# Pure_Power_Strip.net
KiCad netlist of a schematic drawn in EAGLE
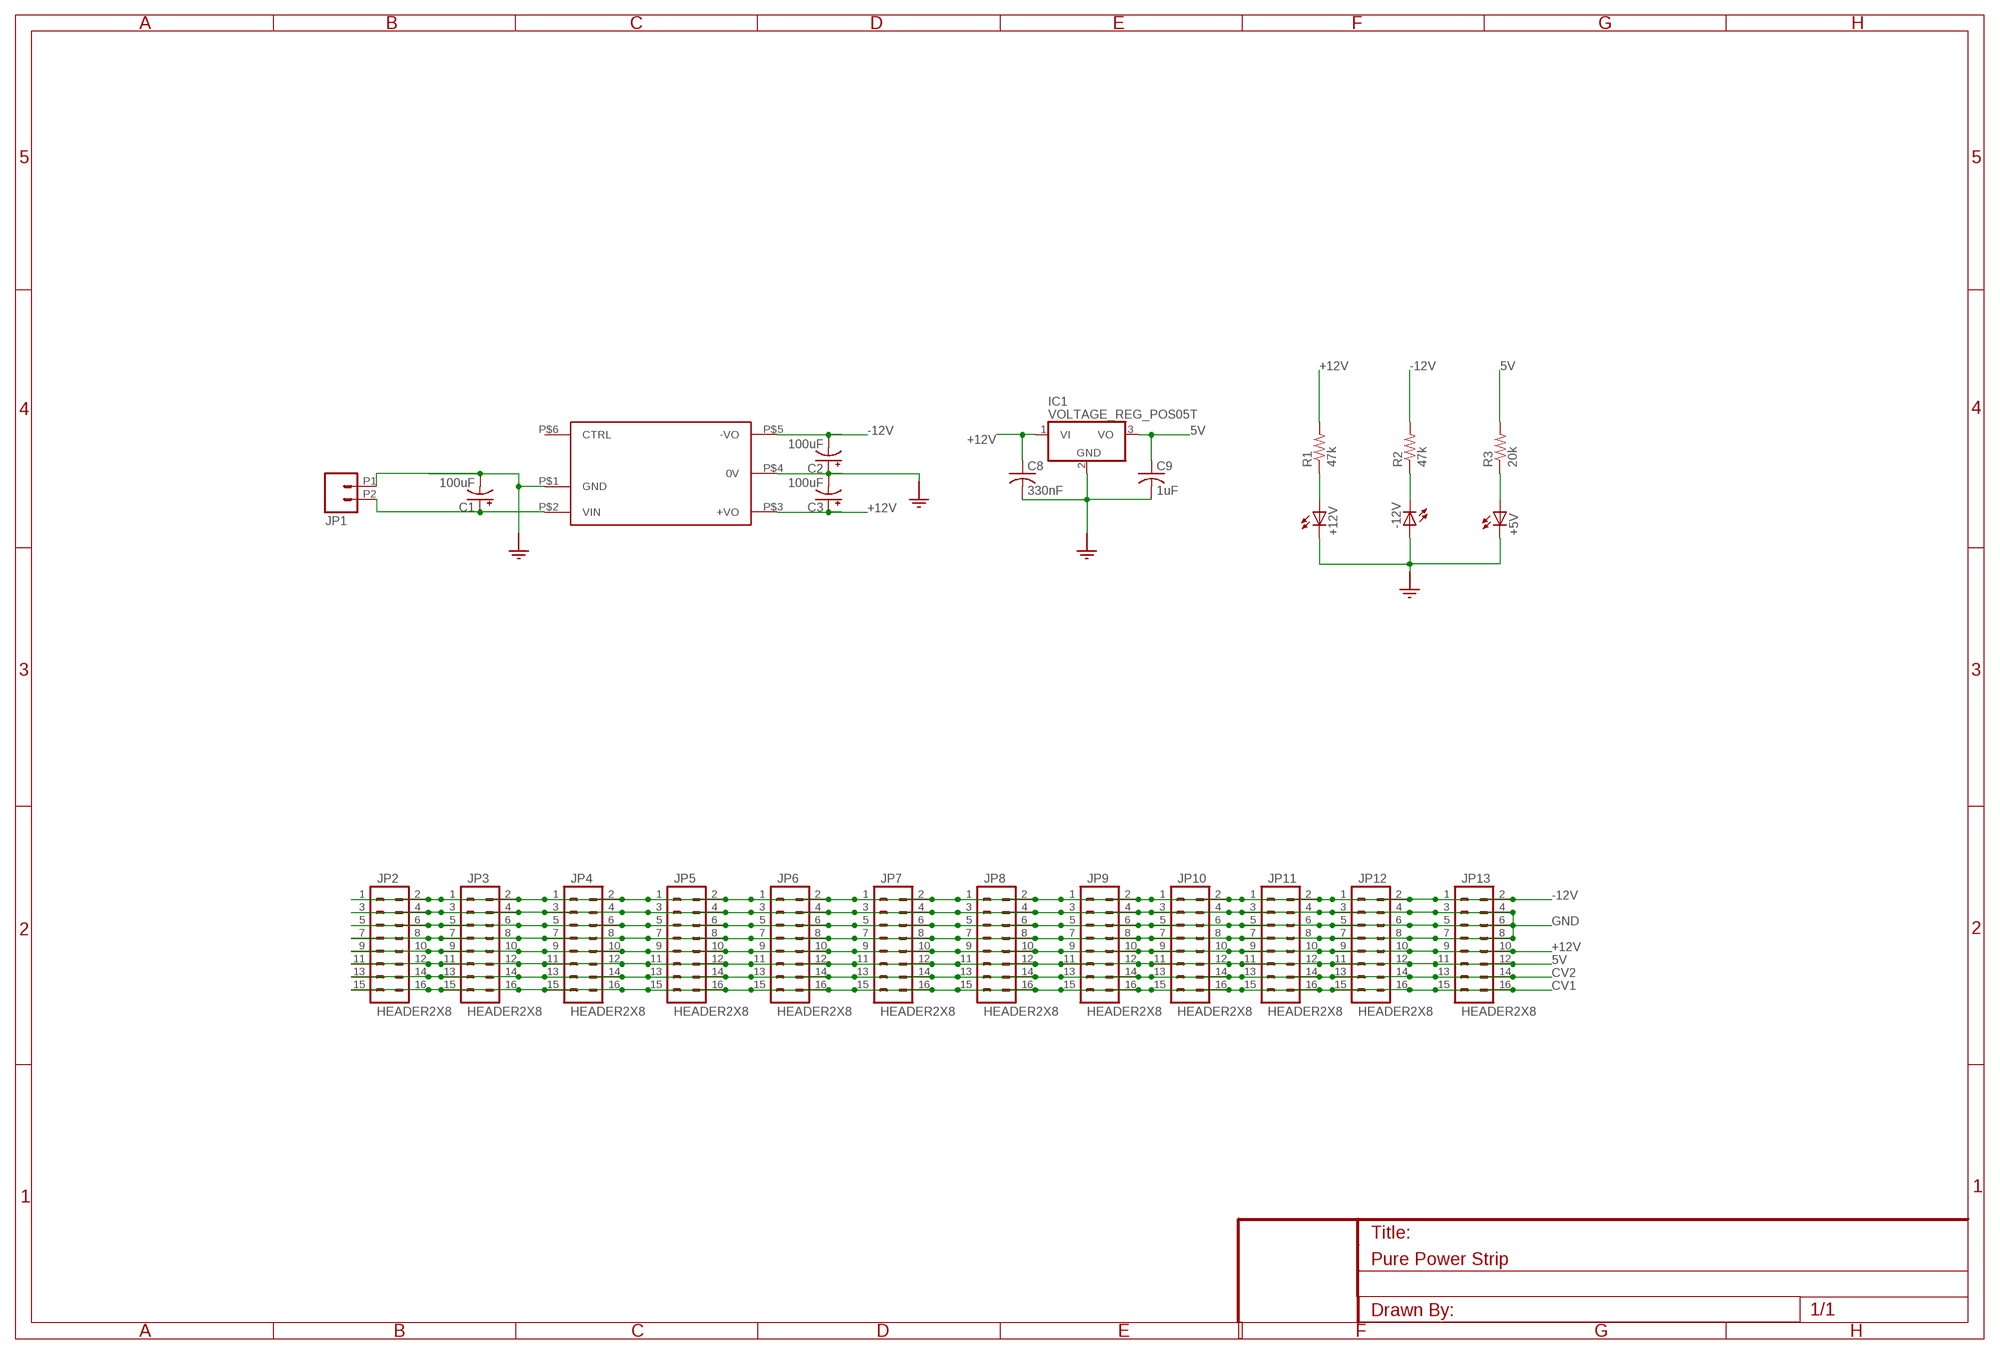
[diagram p0: schematic, sheet 1]

(export (version "E")
  (design (tool "Eeschema 10.0.6"))
  (components
    (comp (ref "+5V")
      (value "LED5MM")
      (footprint "eagle-import:LED5MM")
      (libsource (lib "eagle-import") (part "LED5MM"))
    )
    (comp (ref "+12V")
      (value "LED5MM")
      (footprint "eagle-import:LED5MM")
      (libsource (lib "eagle-import") (part "LED5MM"))
    )
    (comp (ref "-12V")
      (value "LED5MM")
      (footprint "eagle-import:LED5MM")
      (libsource (lib "eagle-import") (part "LED5MM"))
    )
    (comp (ref "C1")
      (value "100uF")
      (footprint "eagle-import:0511_2.24")
      (libsource (lib "eagle-import") (part "CAPACITOR_POL-US0511/2.24"))
    )
    (comp (ref "C2")
      (value "100uF")
      (footprint "eagle-import:0511_2.24")
      (libsource (lib "eagle-import") (part "CAPACITOR_POL-US0511/2.24"))
    )
    (comp (ref "C3")
      (value "100uF")
      (footprint "eagle-import:0511_2.24")
      (libsource (lib "eagle-import") (part "CAPACITOR_POL-US0511/2.24"))
    )
    (comp (ref "C8")
      (value "330nF")
      (footprint "eagle-import:C025-024X044")
      (libsource (lib "eagle-import") (part "CAPACITOR-US025-024X044"))
    )
    (comp (ref "C9")
      (value "1uF")
      (footprint "eagle-import:C025-024X044")
      (libsource (lib "eagle-import") (part "CAPACITOR-US025-024X044"))
    )
    (comp (ref "IC1")
      (value "VOLTAGE_REG_POS05T")
      (footprint "eagle-import:TO220H")
      (libsource (lib "eagle-import") (part "VOLTAGE_REG_POST05"))
    )
    (comp (ref "JP1")
      (value "HEADER1X25MM_SCREWTERM")
      (footprint "eagle-import:1X02_5MM_SCREWTERM")
      (libsource (lib "eagle-import") (part "HEADER1X25MM_SCREWTERM"))
    )
    (comp (ref "JP2")
      (value "HEADER2X8")
      (footprint "eagle-import:POWER_SHROUDED")
      (libsource (lib "eagle-import") (part "HEADER2X8"))
    )
    (comp (ref "JP3")
      (value "HEADER2X8")
      (footprint "eagle-import:POWER_SHROUDED")
      (libsource (lib "eagle-import") (part "HEADER2X8"))
    )
    (comp (ref "JP4")
      (value "HEADER2X8")
      (footprint "eagle-import:POWER_SHROUDED")
      (libsource (lib "eagle-import") (part "HEADER2X8"))
    )
    (comp (ref "JP5")
      (value "HEADER2X8")
      (footprint "eagle-import:POWER_SHROUDED")
      (libsource (lib "eagle-import") (part "HEADER2X8"))
    )
    (comp (ref "JP6")
      (value "HEADER2X8")
      (footprint "eagle-import:POWER_SHROUDED")
      (libsource (lib "eagle-import") (part "HEADER2X8"))
    )
    (comp (ref "JP7")
      (value "HEADER2X8")
      (footprint "eagle-import:POWER_SHROUDED")
      (libsource (lib "eagle-import") (part "HEADER2X8"))
    )
    (comp (ref "JP8")
      (value "HEADER2X8")
      (footprint "eagle-import:POWER_SHROUDED")
      (libsource (lib "eagle-import") (part "HEADER2X8"))
    )
    (comp (ref "JP9")
      (value "HEADER2X8")
      (footprint "eagle-import:POWER_SHROUDED")
      (libsource (lib "eagle-import") (part "HEADER2X8"))
    )
    (comp (ref "JP10")
      (value "HEADER2X8")
      (footprint "eagle-import:POWER_SHROUDED")
      (libsource (lib "eagle-import") (part "HEADER2X8"))
    )
    (comp (ref "JP11")
      (value "HEADER2X8")
      (footprint "eagle-import:POWER_SHROUDED")
      (libsource (lib "eagle-import") (part "HEADER2X8"))
    )
    (comp (ref "JP12")
      (value "HEADER2X8")
      (footprint "eagle-import:POWER_SHROUDED")
      (libsource (lib "eagle-import") (part "HEADER2X8"))
    )
    (comp (ref "JP13")
      (value "HEADER2X8")
      (footprint "eagle-import:POWER_SHROUDED")
      (libsource (lib "eagle-import") (part "HEADER2X8"))
    )
    (comp (ref "R1")
      (value "47k")
      (footprint "eagle-import:0207_8.5")
      (libsource (lib "eagle-import") (part "RESISTOR_US0207/8.5"))
    )
    (comp (ref "R2")
      (value "47k")
      (footprint "eagle-import:0207_8.5")
      (libsource (lib "eagle-import") (part "RESISTOR_US0207/8.5"))
    )
    (comp (ref "R3")
      (value "20k")
      (footprint "eagle-import:0207_8.5")
      (libsource (lib "eagle-import") (part "RESISTOR_US0207/8.5"))
    )
    (comp (ref "U$1")
      (value "DCDC_CONVERTER_URA241XLD-20WR3")
      (footprint "eagle-import:URA241XLD-20WR3")
      (libsource (lib "eagle-import") (part "DCDC_CONVERTER_URA241XLD-20WR3"))
    )
  )
  (nets
    (net (code "1") (name "/+12V") (class "Default")
      (node (ref "C3") (pin "P$2") (pinfunction "+_P$2") (pintype "passive"))
      (node (ref "C8") (pin "1") (pinfunction "1_1") (pintype "passive"))
      (node (ref "IC1") (pin "1") (pinfunction "VI_1") (pintype "input"))
      (node (ref "JP10") (pin "10") (pinfunction "10_10") (pintype "passive"))
      (node (ref "JP10") (pin "9") (pinfunction "9_9") (pintype "passive"))
      (node (ref "JP11") (pin "10") (pinfunction "10_10") (pintype "passive"))
      (node (ref "JP11") (pin "9") (pinfunction "9_9") (pintype "passive"))
      (node (ref "JP12") (pin "10") (pinfunction "10_10") (pintype "passive"))
      (node (ref "JP12") (pin "9") (pinfunction "9_9") (pintype "passive"))
      (node (ref "JP13") (pin "10") (pinfunction "10_10") (pintype "passive"))
      (node (ref "JP13") (pin "9") (pinfunction "9_9") (pintype "passive"))
      (node (ref "JP2") (pin "10") (pinfunction "10_10") (pintype "passive"))
      (node (ref "JP2") (pin "9") (pinfunction "9_9") (pintype "passive"))
      (node (ref "JP3") (pin "10") (pinfunction "10_10") (pintype "passive"))
      (node (ref "JP3") (pin "9") (pinfunction "9_9") (pintype "passive"))
      (node (ref "JP4") (pin "10") (pinfunction "10_10") (pintype "passive"))
      (node (ref "JP4") (pin "9") (pinfunction "9_9") (pintype "passive"))
      (node (ref "JP5") (pin "10") (pinfunction "10_10") (pintype "passive"))
      (node (ref "JP5") (pin "9") (pinfunction "9_9") (pintype "passive"))
      (node (ref "JP6") (pin "10") (pinfunction "10_10") (pintype "passive"))
      (node (ref "JP6") (pin "9") (pinfunction "9_9") (pintype "passive"))
      (node (ref "JP7") (pin "10") (pinfunction "10_10") (pintype "passive"))
      (node (ref "JP7") (pin "9") (pinfunction "9_9") (pintype "passive"))
      (node (ref "JP8") (pin "10") (pinfunction "10_10") (pintype "passive"))
      (node (ref "JP8") (pin "9") (pinfunction "9_9") (pintype "passive"))
      (node (ref "JP9") (pin "10") (pinfunction "10_10") (pintype "passive"))
      (node (ref "JP9") (pin "9") (pinfunction "9_9") (pintype "passive"))
      (node (ref "R1") (pin "2") (pinfunction "2_2") (pintype "passive"))
      (node (ref "U$1") (pin "P$3") (pinfunction "+VO_P$3") (pintype "bidirectional"))
    )
    (net (code "2") (name "/-12V") (class "Default")
      (node (ref "C2") (pin "P$1") (pinfunction "-_P$1") (pintype "passive"))
      (node (ref "JP10") (pin "1") (pinfunction "1_1") (pintype "passive"))
      (node (ref "JP10") (pin "2") (pinfunction "2_2") (pintype "passive"))
      (node (ref "JP11") (pin "1") (pinfunction "1_1") (pintype "passive"))
      (node (ref "JP11") (pin "2") (pinfunction "2_2") (pintype "passive"))
      (node (ref "JP12") (pin "1") (pinfunction "1_1") (pintype "passive"))
      (node (ref "JP12") (pin "2") (pinfunction "2_2") (pintype "passive"))
      (node (ref "JP13") (pin "1") (pinfunction "1_1") (pintype "passive"))
      (node (ref "JP13") (pin "2") (pinfunction "2_2") (pintype "passive"))
      (node (ref "JP2") (pin "1") (pinfunction "1_1") (pintype "passive"))
      (node (ref "JP2") (pin "2") (pinfunction "2_2") (pintype "passive"))
      (node (ref "JP3") (pin "1") (pinfunction "1_1") (pintype "passive"))
      (node (ref "JP3") (pin "2") (pinfunction "2_2") (pintype "passive"))
      (node (ref "JP4") (pin "1") (pinfunction "1_1") (pintype "passive"))
      (node (ref "JP4") (pin "2") (pinfunction "2_2") (pintype "passive"))
      (node (ref "JP5") (pin "1") (pinfunction "1_1") (pintype "passive"))
      (node (ref "JP5") (pin "2") (pinfunction "2_2") (pintype "passive"))
      (node (ref "JP6") (pin "1") (pinfunction "1_1") (pintype "passive"))
      (node (ref "JP6") (pin "2") (pinfunction "2_2") (pintype "passive"))
      (node (ref "JP7") (pin "1") (pinfunction "1_1") (pintype "passive"))
      (node (ref "JP7") (pin "2") (pinfunction "2_2") (pintype "passive"))
      (node (ref "JP8") (pin "1") (pinfunction "1_1") (pintype "passive"))
      (node (ref "JP8") (pin "2") (pinfunction "2_2") (pintype "passive"))
      (node (ref "JP9") (pin "1") (pinfunction "1_1") (pintype "passive"))
      (node (ref "JP9") (pin "2") (pinfunction "2_2") (pintype "passive"))
      (node (ref "R2") (pin "2") (pinfunction "2_2") (pintype "passive"))
      (node (ref "U$1") (pin "P$5") (pinfunction "-VO_P$5") (pintype "bidirectional"))
    )
    (net (code "3") (name "/5V") (class "Default")
      (node (ref "C9") (pin "1") (pinfunction "1_1") (pintype "passive"))
      (node (ref "IC1") (pin "3") (pinfunction "VO_3") (pintype "passive"))
      (node (ref "JP10") (pin "11") (pinfunction "11_11") (pintype "passive"))
      (node (ref "JP10") (pin "12") (pinfunction "12_12") (pintype "passive"))
      (node (ref "JP11") (pin "11") (pinfunction "11_11") (pintype "passive"))
      (node (ref "JP11") (pin "12") (pinfunction "12_12") (pintype "passive"))
      (node (ref "JP12") (pin "11") (pinfunction "11_11") (pintype "passive"))
      (node (ref "JP12") (pin "12") (pinfunction "12_12") (pintype "passive"))
      (node (ref "JP13") (pin "11") (pinfunction "11_11") (pintype "passive"))
      (node (ref "JP13") (pin "12") (pinfunction "12_12") (pintype "passive"))
      (node (ref "JP2") (pin "11") (pinfunction "11_11") (pintype "passive"))
      (node (ref "JP2") (pin "12") (pinfunction "12_12") (pintype "passive"))
      (node (ref "JP3") (pin "11") (pinfunction "11_11") (pintype "passive"))
      (node (ref "JP3") (pin "12") (pinfunction "12_12") (pintype "passive"))
      (node (ref "JP4") (pin "11") (pinfunction "11_11") (pintype "passive"))
      (node (ref "JP4") (pin "12") (pinfunction "12_12") (pintype "passive"))
      (node (ref "JP5") (pin "11") (pinfunction "11_11") (pintype "passive"))
      (node (ref "JP5") (pin "12") (pinfunction "12_12") (pintype "passive"))
      (node (ref "JP6") (pin "11") (pinfunction "11_11") (pintype "passive"))
      (node (ref "JP6") (pin "12") (pinfunction "12_12") (pintype "passive"))
      (node (ref "JP7") (pin "11") (pinfunction "11_11") (pintype "passive"))
      (node (ref "JP7") (pin "12") (pinfunction "12_12") (pintype "passive"))
      (node (ref "JP8") (pin "11") (pinfunction "11_11") (pintype "passive"))
      (node (ref "JP8") (pin "12") (pinfunction "12_12") (pintype "passive"))
      (node (ref "JP9") (pin "11") (pinfunction "11_11") (pintype "passive"))
      (node (ref "JP9") (pin "12") (pinfunction "12_12") (pintype "passive"))
      (node (ref "R3") (pin "2") (pinfunction "2_2") (pintype "passive"))
    )
    (net (code "4") (name "/CV1") (class "Default")
      (node (ref "JP10") (pin "15") (pinfunction "15_15") (pintype "passive"))
      (node (ref "JP10") (pin "16") (pinfunction "16_16") (pintype "passive"))
      (node (ref "JP11") (pin "15") (pinfunction "15_15") (pintype "passive"))
      (node (ref "JP11") (pin "16") (pinfunction "16_16") (pintype "passive"))
      (node (ref "JP12") (pin "15") (pinfunction "15_15") (pintype "passive"))
      (node (ref "JP12") (pin "16") (pinfunction "16_16") (pintype "passive"))
      (node (ref "JP13") (pin "15") (pinfunction "15_15") (pintype "passive"))
      (node (ref "JP13") (pin "16") (pinfunction "16_16") (pintype "passive"))
      (node (ref "JP2") (pin "15") (pinfunction "15_15") (pintype "passive"))
      (node (ref "JP2") (pin "16") (pinfunction "16_16") (pintype "passive"))
      (node (ref "JP3") (pin "15") (pinfunction "15_15") (pintype "passive"))
      (node (ref "JP3") (pin "16") (pinfunction "16_16") (pintype "passive"))
      (node (ref "JP4") (pin "15") (pinfunction "15_15") (pintype "passive"))
      (node (ref "JP4") (pin "16") (pinfunction "16_16") (pintype "passive"))
      (node (ref "JP5") (pin "15") (pinfunction "15_15") (pintype "passive"))
      (node (ref "JP5") (pin "16") (pinfunction "16_16") (pintype "passive"))
      (node (ref "JP6") (pin "15") (pinfunction "15_15") (pintype "passive"))
      (node (ref "JP6") (pin "16") (pinfunction "16_16") (pintype "passive"))
      (node (ref "JP7") (pin "15") (pinfunction "15_15") (pintype "passive"))
      (node (ref "JP7") (pin "16") (pinfunction "16_16") (pintype "passive"))
      (node (ref "JP8") (pin "15") (pinfunction "15_15") (pintype "passive"))
      (node (ref "JP8") (pin "16") (pinfunction "16_16") (pintype "passive"))
      (node (ref "JP9") (pin "15") (pinfunction "15_15") (pintype "passive"))
      (node (ref "JP9") (pin "16") (pinfunction "16_16") (pintype "passive"))
    )
    (net (code "5") (name "/CV2") (class "Default")
      (node (ref "JP10") (pin "13") (pinfunction "13_13") (pintype "passive"))
      (node (ref "JP10") (pin "14") (pinfunction "14_14") (pintype "passive"))
      (node (ref "JP11") (pin "13") (pinfunction "13_13") (pintype "passive"))
      (node (ref "JP11") (pin "14") (pinfunction "14_14") (pintype "passive"))
      (node (ref "JP12") (pin "13") (pinfunction "13_13") (pintype "passive"))
      (node (ref "JP12") (pin "14") (pinfunction "14_14") (pintype "passive"))
      (node (ref "JP13") (pin "13") (pinfunction "13_13") (pintype "passive"))
      (node (ref "JP13") (pin "14") (pinfunction "14_14") (pintype "passive"))
      (node (ref "JP2") (pin "13") (pinfunction "13_13") (pintype "passive"))
      (node (ref "JP2") (pin "14") (pinfunction "14_14") (pintype "passive"))
      (node (ref "JP3") (pin "13") (pinfunction "13_13") (pintype "passive"))
      (node (ref "JP3") (pin "14") (pinfunction "14_14") (pintype "passive"))
      (node (ref "JP4") (pin "13") (pinfunction "13_13") (pintype "passive"))
      (node (ref "JP4") (pin "14") (pinfunction "14_14") (pintype "passive"))
      (node (ref "JP5") (pin "13") (pinfunction "13_13") (pintype "passive"))
      (node (ref "JP5") (pin "14") (pinfunction "14_14") (pintype "passive"))
      (node (ref "JP6") (pin "13") (pinfunction "13_13") (pintype "passive"))
      (node (ref "JP6") (pin "14") (pinfunction "14_14") (pintype "passive"))
      (node (ref "JP7") (pin "13") (pinfunction "13_13") (pintype "passive"))
      (node (ref "JP7") (pin "14") (pinfunction "14_14") (pintype "passive"))
      (node (ref "JP8") (pin "13") (pinfunction "13_13") (pintype "passive"))
      (node (ref "JP8") (pin "14") (pinfunction "14_14") (pintype "passive"))
      (node (ref "JP9") (pin "13") (pinfunction "13_13") (pintype "passive"))
      (node (ref "JP9") (pin "14") (pinfunction "14_14") (pintype "passive"))
    )
    (net (code "6") (name "GND") (class "Default")
      (node (ref "+12V") (pin "K") (pinfunction "C_K") (pintype "passive"))
      (node (ref "+5V") (pin "K") (pinfunction "C_K") (pintype "passive"))
      (node (ref "-12V") (pin "A") (pinfunction "A_A") (pintype "passive"))
      (node (ref "C1") (pin "P$1") (pinfunction "-_P$1") (pintype "passive"))
      (node (ref "C2") (pin "P$2") (pinfunction "+_P$2") (pintype "passive"))
      (node (ref "C3") (pin "P$1") (pinfunction "-_P$1") (pintype "passive"))
      (node (ref "C8") (pin "2") (pinfunction "2_2") (pintype "passive"))
      (node (ref "C9") (pin "2") (pinfunction "2_2") (pintype "passive"))
      (node (ref "IC1") (pin "2") (pinfunction "GND_2") (pintype "passive"))
      (node (ref "JP1") (pin "P1") (pinfunction "1_P1") (pintype "passive"))
      (node (ref "JP10") (pin "3") (pinfunction "3_3") (pintype "passive"))
      (node (ref "JP10") (pin "4") (pinfunction "4_4") (pintype "passive"))
      (node (ref "JP10") (pin "5") (pinfunction "5_5") (pintype "passive"))
      (node (ref "JP10") (pin "6") (pinfunction "6_6") (pintype "passive"))
      (node (ref "JP10") (pin "7") (pinfunction "7_7") (pintype "passive"))
      (node (ref "JP10") (pin "8") (pinfunction "8_8") (pintype "passive"))
      (node (ref "JP11") (pin "3") (pinfunction "3_3") (pintype "passive"))
      (node (ref "JP11") (pin "4") (pinfunction "4_4") (pintype "passive"))
      (node (ref "JP11") (pin "5") (pinfunction "5_5") (pintype "passive"))
      (node (ref "JP11") (pin "6") (pinfunction "6_6") (pintype "passive"))
      (node (ref "JP11") (pin "7") (pinfunction "7_7") (pintype "passive"))
      (node (ref "JP11") (pin "8") (pinfunction "8_8") (pintype "passive"))
      (node (ref "JP12") (pin "3") (pinfunction "3_3") (pintype "passive"))
      (node (ref "JP12") (pin "4") (pinfunction "4_4") (pintype "passive"))
      (node (ref "JP12") (pin "5") (pinfunction "5_5") (pintype "passive"))
      (node (ref "JP12") (pin "6") (pinfunction "6_6") (pintype "passive"))
      (node (ref "JP12") (pin "7") (pinfunction "7_7") (pintype "passive"))
      (node (ref "JP12") (pin "8") (pinfunction "8_8") (pintype "passive"))
      (node (ref "JP13") (pin "3") (pinfunction "3_3") (pintype "passive"))
      (node (ref "JP13") (pin "4") (pinfunction "4_4") (pintype "passive"))
      (node (ref "JP13") (pin "5") (pinfunction "5_5") (pintype "passive"))
      (node (ref "JP13") (pin "6") (pinfunction "6_6") (pintype "passive"))
      (node (ref "JP13") (pin "7") (pinfunction "7_7") (pintype "passive"))
      (node (ref "JP13") (pin "8") (pinfunction "8_8") (pintype "passive"))
      (node (ref "JP2") (pin "3") (pinfunction "3_3") (pintype "passive"))
      (node (ref "JP2") (pin "4") (pinfunction "4_4") (pintype "passive"))
      (node (ref "JP2") (pin "5") (pinfunction "5_5") (pintype "passive"))
      (node (ref "JP2") (pin "6") (pinfunction "6_6") (pintype "passive"))
      (node (ref "JP2") (pin "7") (pinfunction "7_7") (pintype "passive"))
      (node (ref "JP2") (pin "8") (pinfunction "8_8") (pintype "passive"))
      (node (ref "JP3") (pin "3") (pinfunction "3_3") (pintype "passive"))
      (node (ref "JP3") (pin "4") (pinfunction "4_4") (pintype "passive"))
      (node (ref "JP3") (pin "5") (pinfunction "5_5") (pintype "passive"))
      (node (ref "JP3") (pin "6") (pinfunction "6_6") (pintype "passive"))
      (node (ref "JP3") (pin "7") (pinfunction "7_7") (pintype "passive"))
      (node (ref "JP3") (pin "8") (pinfunction "8_8") (pintype "passive"))
      (node (ref "JP4") (pin "3") (pinfunction "3_3") (pintype "passive"))
      (node (ref "JP4") (pin "4") (pinfunction "4_4") (pintype "passive"))
      (node (ref "JP4") (pin "5") (pinfunction "5_5") (pintype "passive"))
      (node (ref "JP4") (pin "6") (pinfunction "6_6") (pintype "passive"))
      (node (ref "JP4") (pin "7") (pinfunction "7_7") (pintype "passive"))
      (node (ref "JP4") (pin "8") (pinfunction "8_8") (pintype "passive"))
      (node (ref "JP5") (pin "3") (pinfunction "3_3") (pintype "passive"))
      (node (ref "JP5") (pin "4") (pinfunction "4_4") (pintype "passive"))
      (node (ref "JP5") (pin "5") (pinfunction "5_5") (pintype "passive"))
      (node (ref "JP5") (pin "6") (pinfunction "6_6") (pintype "passive"))
      (node (ref "JP5") (pin "7") (pinfunction "7_7") (pintype "passive"))
      (node (ref "JP5") (pin "8") (pinfunction "8_8") (pintype "passive"))
      (node (ref "JP6") (pin "3") (pinfunction "3_3") (pintype "passive"))
      (node (ref "JP6") (pin "4") (pinfunction "4_4") (pintype "passive"))
      (node (ref "JP6") (pin "5") (pinfunction "5_5") (pintype "passive"))
      (node (ref "JP6") (pin "6") (pinfunction "6_6") (pintype "passive"))
      (node (ref "JP6") (pin "7") (pinfunction "7_7") (pintype "passive"))
      (node (ref "JP6") (pin "8") (pinfunction "8_8") (pintype "passive"))
      (node (ref "JP7") (pin "3") (pinfunction "3_3") (pintype "passive"))
      (node (ref "JP7") (pin "4") (pinfunction "4_4") (pintype "passive"))
      (node (ref "JP7") (pin "5") (pinfunction "5_5") (pintype "passive"))
      (node (ref "JP7") (pin "6") (pinfunction "6_6") (pintype "passive"))
      (node (ref "JP7") (pin "7") (pinfunction "7_7") (pintype "passive"))
      (node (ref "JP7") (pin "8") (pinfunction "8_8") (pintype "passive"))
      (node (ref "JP8") (pin "3") (pinfunction "3_3") (pintype "passive"))
      (node (ref "JP8") (pin "4") (pinfunction "4_4") (pintype "passive"))
      (node (ref "JP8") (pin "5") (pinfunction "5_5") (pintype "passive"))
      (node (ref "JP8") (pin "6") (pinfunction "6_6") (pintype "passive"))
      (node (ref "JP8") (pin "7") (pinfunction "7_7") (pintype "passive"))
      (node (ref "JP8") (pin "8") (pinfunction "8_8") (pintype "passive"))
      (node (ref "JP9") (pin "3") (pinfunction "3_3") (pintype "passive"))
      (node (ref "JP9") (pin "4") (pinfunction "4_4") (pintype "passive"))
      (node (ref "JP9") (pin "5") (pinfunction "5_5") (pintype "passive"))
      (node (ref "JP9") (pin "6") (pinfunction "6_6") (pintype "passive"))
      (node (ref "JP9") (pin "7") (pinfunction "7_7") (pintype "passive"))
      (node (ref "JP9") (pin "8") (pinfunction "8_8") (pintype "passive"))
      (node (ref "U$1") (pin "P$1") (pinfunction "GND_P$1") (pintype "bidirectional"))
      (node (ref "U$1") (pin "P$4") (pinfunction "0V_P$4") (pintype "bidirectional"))
    )
    (net (code "7") (name "Net-(+5V-PadA)") (class "Default")
      (node (ref "+5V") (pin "A") (pinfunction "A_A") (pintype "passive"))
      (node (ref "R3") (pin "1") (pinfunction "1_1") (pintype "passive"))
    )
    (net (code "8") (name "Net-(+12V-PadA)") (class "Default")
      (node (ref "+12V") (pin "A") (pinfunction "A_A") (pintype "passive"))
      (node (ref "R1") (pin "1") (pinfunction "1_1") (pintype "passive"))
    )
    (net (code "9") (name "Net-(-12V-C)") (class "Default")
      (node (ref "-12V") (pin "K") (pinfunction "C_K") (pintype "passive"))
      (node (ref "R2") (pin "1") (pinfunction "1_1") (pintype "passive"))
    )
    (net (code "10") (name "Net-(C1-+)") (class "Default")
      (node (ref "C1") (pin "P$2") (pinfunction "+_P$2") (pintype "passive"))
      (node (ref "JP1") (pin "P2") (pinfunction "2_P2") (pintype "passive"))
      (node (ref "U$1") (pin "P$2") (pinfunction "VIN_P$2") (pintype "bidirectional"))
    )
    (net (code "11") (name "unconnected-(U$1-CTRL-PadP$6)") (class "Default")
      (node (ref "U$1") (pin "P$6") (pinfunction "CTRL_P$6") (pintype "bidirectional"))
    )
  )
)
